# ADC.net
KiCad netlist of a schematic drawn in Altium Designer
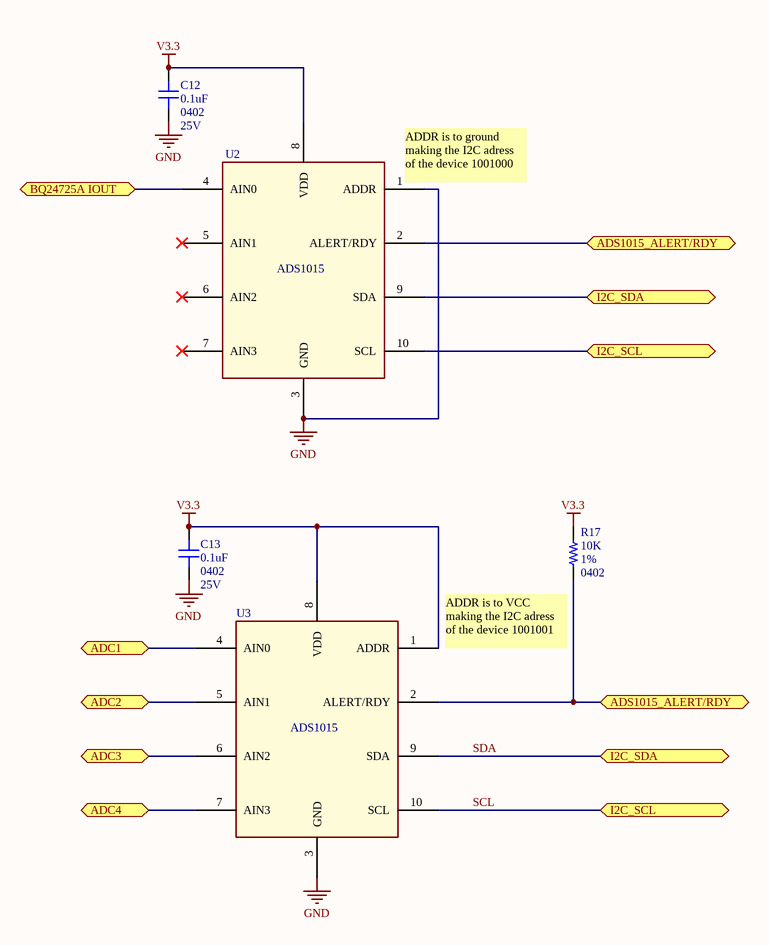
[diagram p0: ADC.SchDoc]

(export (version "E")
  (design (tool "Eeschema 10.0.6"))
  (components
    (comp (ref "C12")
      (value "0.1uF")
      (footprint "CAP_0402")
      (description "CAP - 0402")
      (fields
        (field (name "PART NUMBER") "CL05A104KA5NNNC")
        (field (name "PACKAGE") "0402")
        (field (name "VOLTAGE") "25V")
      )
      (libsource (lib "SecureBot") (part "CAP - 0402"))
    )
    (comp (ref "C13")
      (value "0.1uF")
      (footprint "CAP_0402")
      (description "CAP - 0402")
      (fields
        (field (name "PART NUMBER") "CL05A104KA5NNNC")
        (field (name "PACKAGE") "0402")
        (field (name "VOLTAGE") "25V")
      )
      (libsource (lib "SecureBot") (part "CAP - 0402"))
    )
    (comp (ref "R17")
      (value "10K")
      (footprint "RES_0402")
      (description "RES - 0402")
      (fields
        (field (name "PART NUMBER") "MCS0402MC1002FE000")
        (field (name "TOLERANCE") "1%")
        (field (name "PACKAGE") "0402")
      )
      (libsource (lib "SecureBot") (part "RES - 0402"))
    )
    (comp (ref "U2") (value "ADS1015") (footprint "ADS1015") (libsource (lib "SecureBot") (part "ADS1015")))
    (comp (ref "U3") (value "ADS1015") (footprint "ADS1015") (libsource (lib "SecureBot") (part "ADS1015")))
  )
  (nets
    (net (code "1") (name "/ADC1") (class "Default")
      (node (ref "U3") (pin "4") (pinfunction "AIN0_4") (pintype "passive"))
    )
    (net (code "2") (name "/ADC2") (class "Default")
      (node (ref "U3") (pin "5") (pinfunction "AIN1_5") (pintype "passive"))
    )
    (net (code "3") (name "/ADC3") (class "Default")
      (node (ref "U3") (pin "6") (pinfunction "AIN2_6") (pintype "passive"))
    )
    (net (code "4") (name "/ADC4") (class "Default")
      (node (ref "U3") (pin "7") (pinfunction "AIN3_7") (pintype "passive"))
    )
    (net (code "5") (name "/ADS1015_ALERT{slash}RDY") (class "Default")
      (node (ref "R17") (pin "2") (pinfunction "2_2") (pintype "passive"))
      (node (ref "U2") (pin "2") (pinfunction "ALERT/RDY_2") (pintype "passive"))
      (node (ref "U3") (pin "2") (pinfunction "ALERT/RDY_2") (pintype "passive"))
    )
    (net (code "6") (name "/BQ24725A IOUT") (class "Default")
      (node (ref "U2") (pin "4") (pinfunction "AIN0_4") (pintype "passive"))
    )
    (net (code "7") (name "/SCL") (class "Default")
      (node (ref "U2") (pin "10") (pinfunction "SCL_10") (pintype "passive"))
      (node (ref "U3") (pin "10") (pinfunction "SCL_10") (pintype "passive"))
    )
    (net (code "8") (name "/SDA") (class "Default")
      (node (ref "U2") (pin "9") (pinfunction "SDA_9") (pintype "passive"))
      (node (ref "U3") (pin "9") (pinfunction "SDA_9") (pintype "passive"))
    )
    (net (code "9") (name "GND") (class "Default")
      (node (ref "C12") (pin "2") (pinfunction "2_2") (pintype "passive"))
      (node (ref "C13") (pin "2") (pinfunction "2_2") (pintype "passive"))
      (node (ref "U2") (pin "1") (pinfunction "ADDR_1") (pintype "passive"))
      (node (ref "U2") (pin "3") (pinfunction "GND_3") (pintype "passive"))
      (node (ref "U3") (pin "3") (pinfunction "GND_3") (pintype "passive"))
    )
    (net (code "10") (name "V3.3") (class "Default")
      (node (ref "C12") (pin "1") (pinfunction "1_1") (pintype "passive"))
      (node (ref "C13") (pin "1") (pinfunction "1_1") (pintype "passive"))
      (node (ref "R17") (pin "1") (pinfunction "1_1") (pintype "passive"))
      (node (ref "U2") (pin "8") (pinfunction "VDD_8") (pintype "passive"))
      (node (ref "U3") (pin "1") (pinfunction "ADDR_1") (pintype "passive"))
      (node (ref "U3") (pin "8") (pinfunction "VDD_8") (pintype "passive"))
    )
    (net (code "11") (name "unconnected-(U2-AIN1-Pad5)") (class "Default")
      (node (ref "U2") (pin "5") (pinfunction "AIN1_5") (pintype "passive+no_connect"))
    )
    (net (code "12") (name "unconnected-(U2-AIN2-Pad6)") (class "Default")
      (node (ref "U2") (pin "6") (pinfunction "AIN2_6") (pintype "passive+no_connect"))
    )
    (net (code "13") (name "unconnected-(U2-AIN3-Pad7)") (class "Default")
      (node (ref "U2") (pin "7") (pinfunction "AIN3_7") (pintype "passive+no_connect"))
    )
  )
)
